# Transceiver.net
KiCad netlist of a schematic drawn in Altium Designer
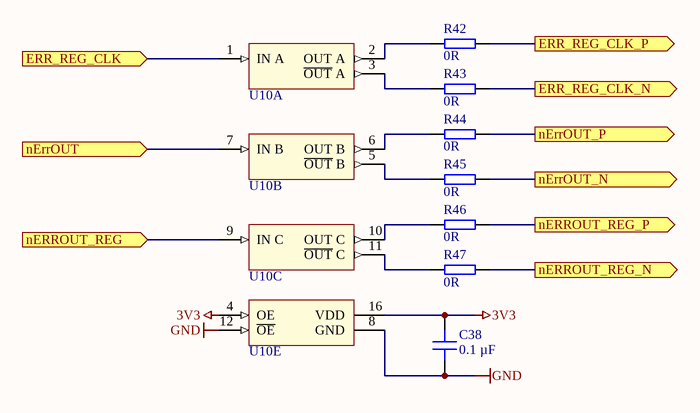
[diagram p0: Transceiver.SchDoc]

(export (version "E")
  (design (tool "Eeschema 10.0.6"))
  (components
    (comp (ref "C38")
      (value "0.1 µF")
      (footprint "C_0603")
      (description "Capacitor 0603, 50 VDC, 0.1 µF, X7R")
      (fields
        (field (name "MANUFACTURER PART NUMBER") "C0603X104K5RAC7411")
        (field (name "MANUFACTURER") "KEMET")
        (field (name "CREATED FROM") "MGremer")
      )
      (libsource (lib "user") (part "Capacitor"))
    )
    (comp (ref "R42")
      (value "0R")
      (footprint "RES 0603_1608")
      (description "SMD resistor E24 series")
      (fields
        (field (name "MANUFACTURER PART NUMBER") "RC0603JR-070RL")
        (field (name "MANUFACTURER") "YAGEO")
        (field (name "CREATED FROM") "MGremer")
      )
      (libsource (lib "user") (part "Resistor"))
    )
    (comp (ref "R43")
      (value "0R")
      (footprint "RES 0603_1608")
      (description "SMD resistor E24 series")
      (fields
        (field (name "MANUFACTURER PART NUMBER") "RC0603JR-070RL")
        (field (name "MANUFACTURER") "YAGEO")
        (field (name "CREATED FROM") "MGremer")
      )
      (libsource (lib "user") (part "Resistor"))
    )
    (comp (ref "R44")
      (value "0R")
      (footprint "RES 0603_1608")
      (description "SMD resistor E24 series")
      (fields
        (field (name "MANUFACTURER PART NUMBER") "RC0603JR-070RL")
        (field (name "MANUFACTURER") "YAGEO")
        (field (name "CREATED FROM") "MGremer")
      )
      (libsource (lib "user") (part "Resistor"))
    )
    (comp (ref "R45")
      (value "0R")
      (footprint "RES 0603_1608")
      (description "SMD resistor E24 series")
      (fields
        (field (name "MANUFACTURER PART NUMBER") "RC0603JR-070RL")
        (field (name "MANUFACTURER") "YAGEO")
        (field (name "CREATED FROM") "MGremer")
      )
      (libsource (lib "user") (part "Resistor"))
    )
    (comp (ref "R46")
      (value "0R")
      (footprint "RES 0603_1608")
      (description "SMD resistor E24 series")
      (fields
        (field (name "MANUFACTURER PART NUMBER") "RC0603JR-070RL")
        (field (name "MANUFACTURER") "YAGEO")
        (field (name "CREATED FROM") "MGremer")
      )
      (libsource (lib "user") (part "Resistor"))
    )
    (comp (ref "R47")
      (value "0R")
      (footprint "RES 0603_1608")
      (description "SMD resistor E24 series")
      (fields
        (field (name "MANUFACTURER PART NUMBER") "RC0603JR-070RL")
        (field (name "MANUFACTURER") "YAGEO")
        (field (name "CREATED FROM") "MGremer")
      )
      (libsource (lib "user") (part "Resistor"))
    )
    (comp (ref "U10")
      (value "DS26C31TMX/NOPB")
      (footprint "TI_D-R-PDSO-G16_N")
      (description "CMOS Quad Tri-State Differential Line Drivers, 16-pin Narrow SOIC, Pb-Free")
      (fields
        (field (name "MANUFACTURER") "Texas Instruments")
        (field (name "LCSC PART NUMBER") "C132085")
        (field (name "CREATED FROM") "T. Wendt")
      )
      (libsource (lib "user") (part "DS26C31TMX"))
    )
  )
  (nets
    (net (code "1") (name "/ERR_REG_CLK") (class "Default")
      (node (ref "U10") (pin "1") (pinfunction "IN_A_1") (pintype "input"))
    )
    (net (code "2") (name "/ERR_REG_CLK_N") (class "Default")
      (node (ref "R43") (pin "2") (pinfunction "2_2") (pintype "passive"))
    )
    (net (code "3") (name "/ERR_REG_CLK_P") (class "Default")
      (node (ref "R42") (pin "2") (pinfunction "2_2") (pintype "passive"))
    )
    (net (code "4") (name "/nERROUT_REG") (class "Default")
      (node (ref "U10") (pin "9") (pinfunction "IN_C_9") (pintype "input"))
    )
    (net (code "5") (name "/nERROUT_REG_N") (class "Default")
      (node (ref "R47") (pin "2") (pinfunction "2_2") (pintype "passive"))
    )
    (net (code "6") (name "/nERROUT_REG_P") (class "Default")
      (node (ref "R46") (pin "2") (pinfunction "2_2") (pintype "passive"))
    )
    (net (code "7") (name "/nErrOUT") (class "Default")
      (node (ref "U10") (pin "7") (pinfunction "IN_B_7") (pintype "input"))
    )
    (net (code "8") (name "/nErrOUT_N") (class "Default")
      (node (ref "R45") (pin "2") (pinfunction "2_2") (pintype "passive"))
    )
    (net (code "9") (name "/nErrOUT_P") (class "Default")
      (node (ref "R44") (pin "2") (pinfunction "2_2") (pintype "passive"))
    )
    (net (code "10") (name "3V3") (class "Default")
      (node (ref "C38") (pin "2") (pinfunction "2_2") (pintype "passive"))
      (node (ref "U10") (pin "16") (pinfunction "VDD_16") (pintype "power_in"))
      (node (ref "U10") (pin "4") (pinfunction "OE_4") (pintype "input"))
    )
    (net (code "11") (name "GND") (class "Default")
      (node (ref "C38") (pin "1") (pinfunction "1_1") (pintype "passive"))
      (node (ref "U10") (pin "12") (pinfunction "~{OE}_12") (pintype "input"))
      (node (ref "U10") (pin "8") (pinfunction "GND_8") (pintype "power_in"))
    )
    (net (code "12") (name "Net-(U10A-OUT_A)") (class "Default")
      (node (ref "R42") (pin "1") (pinfunction "1_1") (pintype "passive"))
      (node (ref "U10") (pin "2") (pinfunction "OUT_A_2") (pintype "output"))
    )
    (net (code "13") (name "Net-(U10A-~{OUT}_A)") (class "Default")
      (node (ref "R43") (pin "1") (pinfunction "1_1") (pintype "passive"))
      (node (ref "U10") (pin "3") (pinfunction "~{OUT}_A_3") (pintype "output"))
    )
    (net (code "14") (name "Net-(U10B-OUT_B)") (class "Default")
      (node (ref "R44") (pin "1") (pinfunction "1_1") (pintype "passive"))
      (node (ref "U10") (pin "6") (pinfunction "OUT_B_6") (pintype "output"))
    )
    (net (code "15") (name "Net-(U10B-~{OUT}_B)") (class "Default")
      (node (ref "R45") (pin "1") (pinfunction "1_1") (pintype "passive"))
      (node (ref "U10") (pin "5") (pinfunction "~{OUT}_B_5") (pintype "output"))
    )
    (net (code "16") (name "Net-(U10C-OUT_C)") (class "Default")
      (node (ref "R46") (pin "1") (pinfunction "1_1") (pintype "passive"))
      (node (ref "U10") (pin "10") (pinfunction "OUT_C_10") (pintype "output"))
    )
    (net (code "17") (name "Net-(U10C-~{OUT}_C)") (class "Default")
      (node (ref "R47") (pin "1") (pinfunction "1_1") (pintype "passive"))
      (node (ref "U10") (pin "11") (pinfunction "~{OUT}_C_11") (pintype "output"))
    )
  )
)
